# LAB-PPS330D.net
KiCad netlist of a schematic drawn in EAGLE
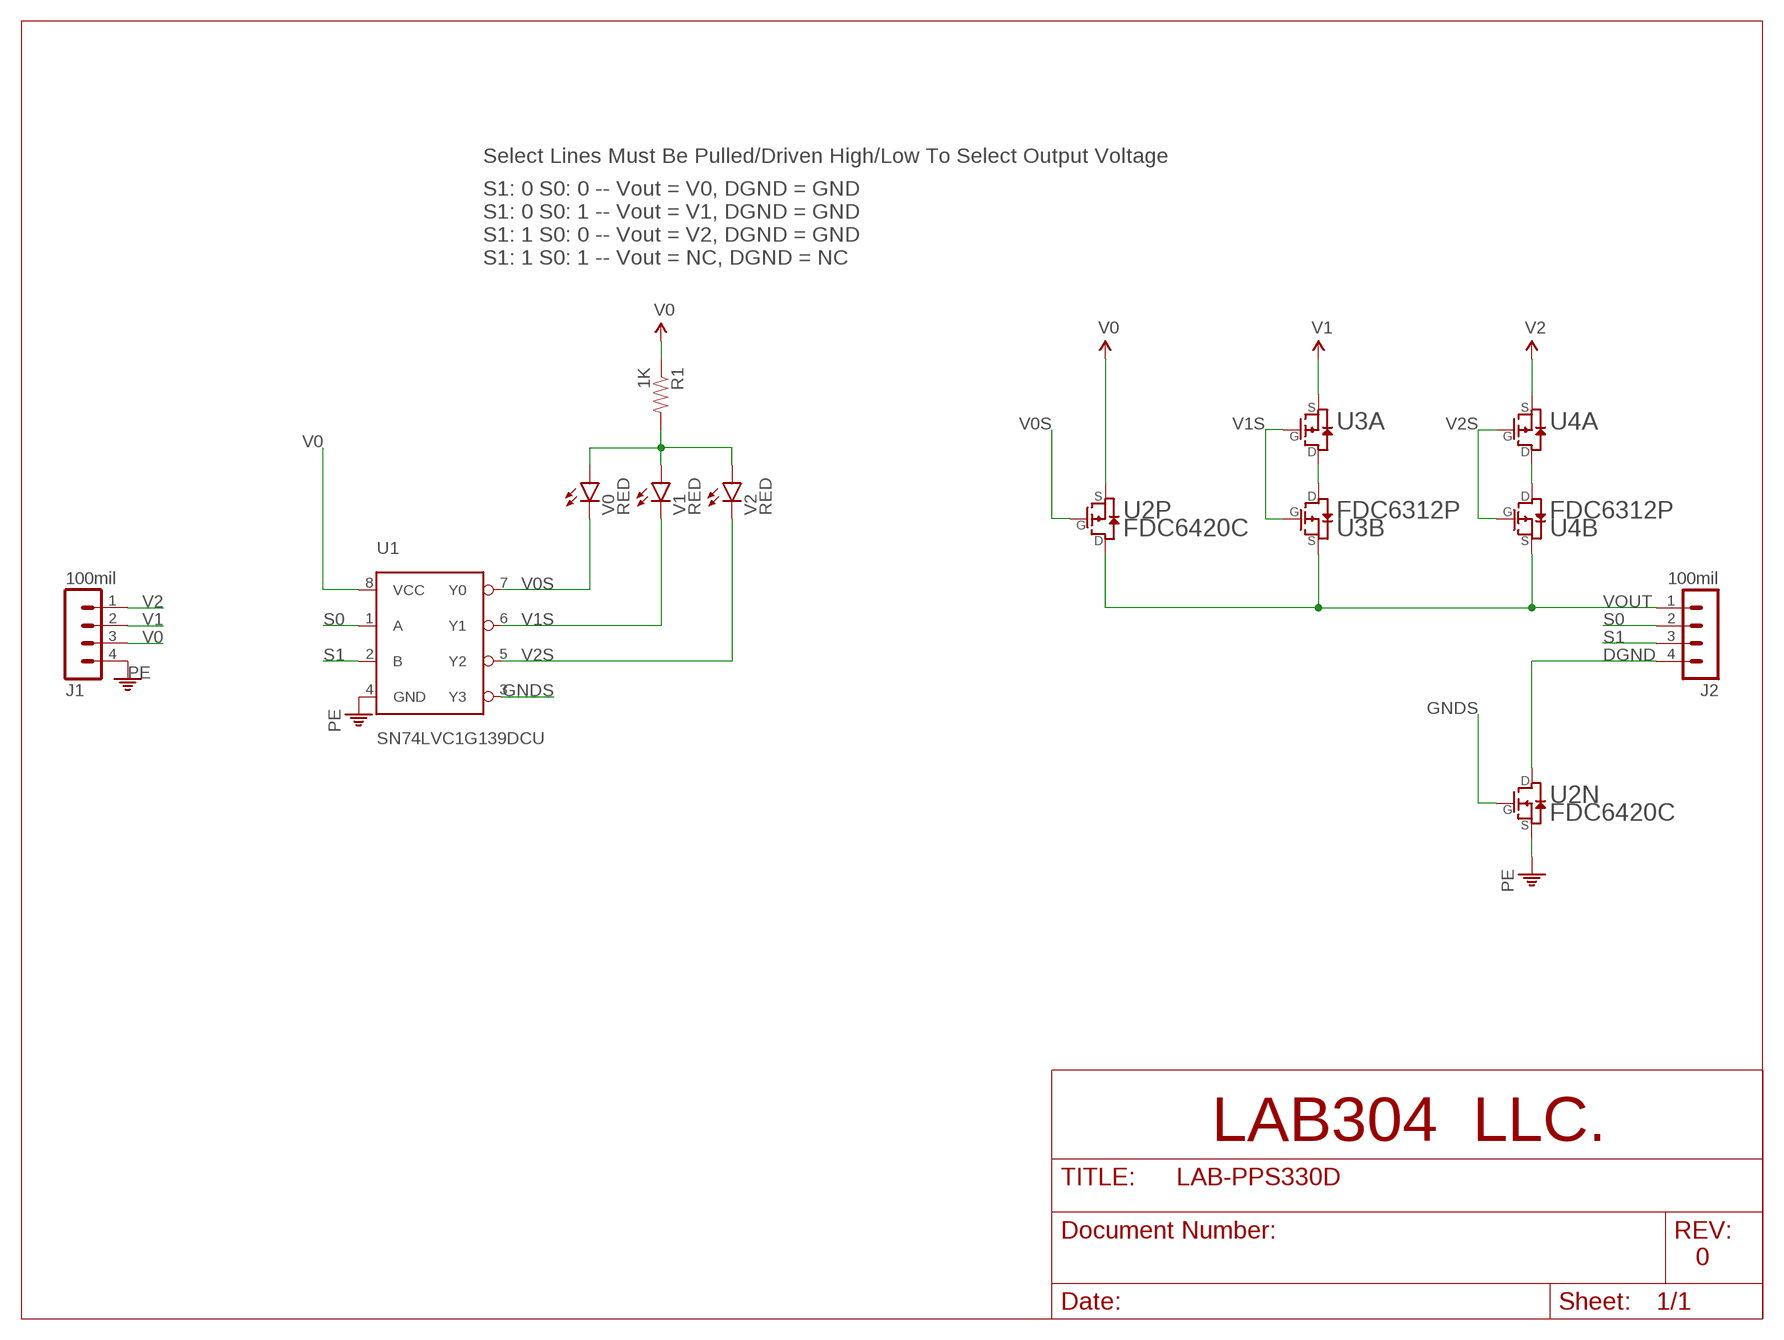
[diagram p0: schematic, sheet 1]

(export (version "E")
  (design (tool "Eeschema 10.0.6"))
  (components
    (comp (ref "J1")
      (value "100mil")
      (footprint "eagle-import:MA04-1")
      (libsource (lib "eagle-import") (part "MA04-1"))
    )
    (comp (ref "J2")
      (value "100mil")
      (footprint "eagle-import:MA04-1")
      (libsource (lib "eagle-import") (part "MA04-1"))
    )
    (comp (ref "R1")
      (value "1K")
      (footprint "eagle-import:0603-RES")
      (libsource (lib "eagle-import") (part "1KOHM-1/10W-1%(0603)"))
    )
    (comp (ref "U1")
      (value "SN74LVC1G139DCU")
      (footprint "eagle-import:SOP50P310X90-8N")
      (libsource (lib "eagle-import") (part "SN74LVC1G139DCU"))
    )
    (comp (ref "U2")
      (value "FDC6420C")
      (footprint "eagle-import:SOT95P270X145-6N")
      (libsource (lib "eagle-import") (part "FDC6420C"))
    )
    (comp (ref "U3")
      (value "FDC6312P")
      (footprint "eagle-import:SOT95P270X145-6N")
      (libsource (lib "eagle-import") (part "FDC6312P"))
    )
    (comp (ref "U4")
      (value "FDC6312P")
      (footprint "eagle-import:SOT95P270X145-6N")
      (libsource (lib "eagle-import") (part "FDC6312P"))
    )
    (comp (ref "V0")
      (value "RED")
      (footprint "eagle-import:LED-0603")
      (libsource (lib "eagle-import") (part "LED-RED0603"))
    )
    (comp (ref "V1")
      (value "RED")
      (footprint "eagle-import:LED-0603")
      (libsource (lib "eagle-import") (part "LED-RED0603"))
    )
    (comp (ref "V2")
      (value "RED")
      (footprint "eagle-import:LED-0603")
      (libsource (lib "eagle-import") (part "LED-RED0603"))
    )
  )
  (nets
    (net (code "1") (name "/DGND") (class "Default")
      (node (ref "J2") (pin "4") (pinfunction "4_4") (pintype "passive"))
      (node (ref "U2") (pin "6") (pinfunction "D_6") (pintype "bidirectional"))
    )
    (net (code "2") (name "/GNDS") (class "Default")
      (node (ref "U1") (pin "3") (pinfunction "Y3_3") (pintype "bidirectional"))
      (node (ref "U2") (pin "1") (pinfunction "G_1") (pintype "bidirectional"))
    )
    (net (code "3") (name "/S0") (class "Default")
      (node (ref "J2") (pin "2") (pinfunction "2_2") (pintype "passive"))
      (node (ref "U1") (pin "1") (pinfunction "A_1") (pintype "bidirectional"))
    )
    (net (code "4") (name "/S1") (class "Default")
      (node (ref "J2") (pin "3") (pinfunction "3_3") (pintype "passive"))
      (node (ref "U1") (pin "2") (pinfunction "B_2") (pintype "bidirectional"))
    )
    (net (code "5") (name "/V0S") (class "Default")
      (node (ref "U1") (pin "7") (pinfunction "Y0_7") (pintype "bidirectional"))
      (node (ref "U2") (pin "3") (pinfunction "G_3") (pintype "bidirectional"))
      (node (ref "V0") (pin "C") (pinfunction "C_C") (pintype "passive"))
    )
    (net (code "6") (name "/V1S") (class "Default")
      (node (ref "U1") (pin "6") (pinfunction "Y1_6") (pintype "bidirectional"))
      (node (ref "U3") (pin "1") (pinfunction "G_1") (pintype "bidirectional"))
      (node (ref "U3") (pin "3") (pinfunction "G_3") (pintype "bidirectional"))
      (node (ref "V1") (pin "C") (pinfunction "C_C") (pintype "passive"))
    )
    (net (code "7") (name "/V2S") (class "Default")
      (node (ref "U1") (pin "5") (pinfunction "Y2_5") (pintype "bidirectional"))
      (node (ref "U4") (pin "1") (pinfunction "G_1") (pintype "bidirectional"))
      (node (ref "U4") (pin "3") (pinfunction "G_3") (pintype "bidirectional"))
      (node (ref "V2") (pin "C") (pinfunction "C_C") (pintype "passive"))
    )
    (net (code "8") (name "/VOUT") (class "Default")
      (node (ref "J2") (pin "1") (pinfunction "1_1") (pintype "passive"))
      (node (ref "U2") (pin "4") (pinfunction "D_4") (pintype "bidirectional"))
      (node (ref "U3") (pin "2") (pinfunction "S_2") (pintype "bidirectional"))
      (node (ref "U4") (pin "2") (pinfunction "S_2") (pintype "bidirectional"))
    )
    (net (code "9") (name "Net-(R1-Pad2)") (class "Default")
      (node (ref "R1") (pin "2") (pinfunction "2_2") (pintype "passive"))
      (node (ref "V0") (pin "A") (pinfunction "A_A") (pintype "passive"))
      (node (ref "V1") (pin "A") (pinfunction "A_A") (pintype "passive"))
      (node (ref "V2") (pin "A") (pinfunction "A_A") (pintype "passive"))
    )
    (net (code "10") (name "Net-(U3A-D)") (class "Default")
      (node (ref "U3") (pin "4") (pinfunction "D_4") (pintype "bidirectional"))
      (node (ref "U3") (pin "6") (pinfunction "D_6") (pintype "bidirectional"))
    )
    (net (code "11") (name "Net-(U4A-D)") (class "Default")
      (node (ref "U4") (pin "4") (pinfunction "D_4") (pintype "bidirectional"))
      (node (ref "U4") (pin "6") (pinfunction "D_6") (pintype "bidirectional"))
    )
    (net (code "12") (name "PE") (class "Default")
      (node (ref "J1") (pin "4") (pinfunction "4_4") (pintype "passive"))
      (node (ref "U1") (pin "4") (pinfunction "GND_4") (pintype "bidirectional"))
      (node (ref "U2") (pin "5") (pinfunction "S_5") (pintype "bidirectional"))
    )
    (net (code "13") (name "V0") (class "Default")
      (node (ref "J1") (pin "3") (pinfunction "3_3") (pintype "passive"))
      (node (ref "R1") (pin "1") (pinfunction "1_1") (pintype "passive"))
      (node (ref "U1") (pin "8") (pinfunction "VCC_8") (pintype "bidirectional"))
      (node (ref "U2") (pin "2") (pinfunction "S_2") (pintype "bidirectional"))
    )
    (net (code "14") (name "V1") (class "Default")
      (node (ref "J1") (pin "2") (pinfunction "2_2") (pintype "passive"))
      (node (ref "U3") (pin "5") (pinfunction "S_5") (pintype "bidirectional"))
    )
    (net (code "15") (name "V2") (class "Default")
      (node (ref "J1") (pin "1") (pinfunction "1_1") (pintype "passive"))
      (node (ref "U4") (pin "5") (pinfunction "S_5") (pintype "bidirectional"))
    )
  )
)
